# MIC3.net
KiCad netlist of a schematic drawn in Altium Designer
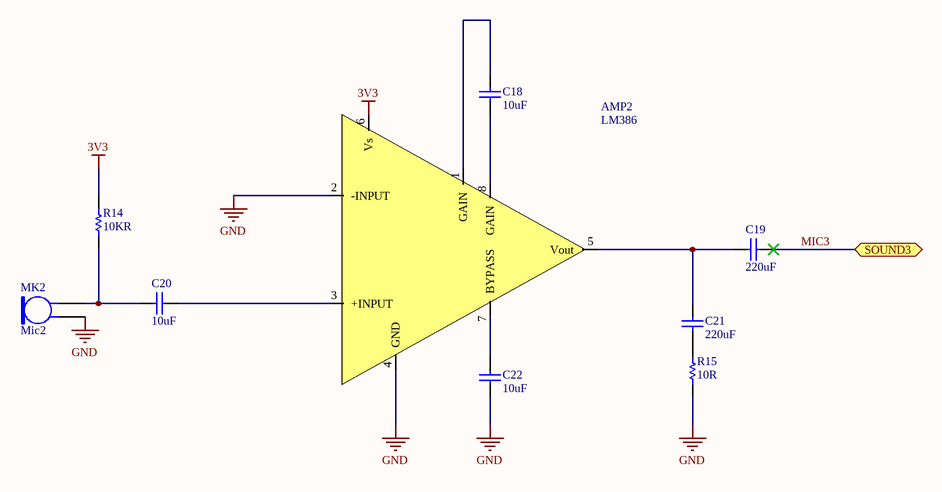
[diagram p0: MIC3.SchDoc]

(export (version "E")
  (design (tool "Eeschema 10.0.6"))
  (components
    (comp (ref "AMP2") (value "LM386") (footprint "Ampli") (libsource (lib "SCHLIB_Autobot") (part "LM386")))
    (comp (ref "C18")
      (value "10uF")
      (footprint "CAPC1608N")
      (description "Capacitor")
      (fields (field (name "PUBLISHER") "Altium Limited"))
      (libsource (lib "Miscellaneous Devices") (part "Cap"))
    )
    (comp (ref "C19")
      (value "220uF")
      (footprint "CAPC1608N")
      (description "Capacitor")
      (fields (field (name "PUBLISHER") "Altium Limited"))
      (libsource (lib "Miscellaneous Devices") (part "Cap"))
    )
    (comp (ref "C20")
      (value "10uF")
      (footprint "CAPC1608N")
      (description "Capacitor")
      (fields (field (name "PUBLISHER") "Altium Limited"))
      (libsource (lib "Miscellaneous Devices") (part "Cap"))
    )
    (comp (ref "C21")
      (value "220uF")
      (footprint "CAPC1608N")
      (description "Capacitor")
      (fields (field (name "PUBLISHER") "Altium Limited"))
      (libsource (lib "Miscellaneous Devices") (part "Cap"))
    )
    (comp (ref "C22")
      (value "10uF")
      (footprint "CAPC1608N")
      (description "Capacitor")
      (fields (field (name "PUBLISHER") "Altium Limited"))
      (libsource (lib "Miscellaneous Devices") (part "Cap"))
    )
    (comp (ref "MK2")
      (value "Mic2")
      (footprint "PIN2")
      (description "Microphone")
      (fields (field (name "PUBLISHER") "Altium Limited"))
      (libsource (lib "Miscellaneous Devices") (part "Mic2"))
    )
    (comp (ref "R14")
      (value "10KR")
      (footprint "RESC1608N")
      (description "Resistor")
      (fields (field (name "PUBLISHER") "Altium Limited"))
      (libsource (lib "Miscellaneous Devices") (part "Res1"))
    )
    (comp (ref "R15")
      (value "10R")
      (footprint "RESC1608N")
      (description "Resistor")
      (fields (field (name "PUBLISHER") "Altium Limited"))
      (libsource (lib "Miscellaneous Devices") (part "Res1"))
    )
  )
  (nets
    (net (code "1") (name "/MIC3") (class "Default")
      (node (ref "C19") (pin "1") (pinfunction "1_1") (pintype "passive+no_connect"))
    )
    (net (code "2") (name "3V3") (class "Default")
      (node (ref "AMP2") (pin "6") (pinfunction "Vs_6") (pintype "passive"))
      (node (ref "R14") (pin "1") (pinfunction "1_1") (pintype "passive"))
    )
    (net (code "3") (name "GND") (class "Default")
      (node (ref "AMP2") (pin "2") (pinfunction "-INPUT_2") (pintype "passive"))
      (node (ref "AMP2") (pin "4") (pinfunction "GND_4") (pintype "passive"))
      (node (ref "C22") (pin "2") (pinfunction "2_2") (pintype "passive"))
      (node (ref "MK2") (pin "1") (pinfunction "1_1") (pintype "passive"))
      (node (ref "R15") (pin "2") (pinfunction "2_2") (pintype "passive"))
    )
    (net (code "4") (name "Net-(AMP2-+INPUT)") (class "Default")
      (node (ref "AMP2") (pin "3") (pinfunction "+INPUT_3") (pintype "passive"))
      (node (ref "C20") (pin "1") (pinfunction "1_1") (pintype "passive"))
    )
    (net (code "5") (name "Net-(AMP2-BYPASS)") (class "Default")
      (node (ref "AMP2") (pin "7") (pinfunction "BYPASS_7") (pintype "passive"))
      (node (ref "C22") (pin "1") (pinfunction "1_1") (pintype "passive"))
    )
    (net (code "6") (name "Net-(AMP2-GAIN-Pad1)") (class "Default")
      (node (ref "AMP2") (pin "1") (pinfunction "GAIN_1") (pintype "passive"))
      (node (ref "C18") (pin "1") (pinfunction "1_1") (pintype "passive"))
    )
    (net (code "7") (name "Net-(AMP2-GAIN-Pad8)") (class "Default")
      (node (ref "AMP2") (pin "8") (pinfunction "GAIN_8") (pintype "passive"))
      (node (ref "C18") (pin "2") (pinfunction "2_2") (pintype "passive"))
    )
    (net (code "8") (name "Net-(AMP2-Vout)") (class "Default")
      (node (ref "AMP2") (pin "5") (pinfunction "Vout_5") (pintype "passive"))
      (node (ref "C19") (pin "2") (pinfunction "2_2") (pintype "passive"))
      (node (ref "C21") (pin "1") (pinfunction "1_1") (pintype "passive"))
    )
    (net (code "9") (name "Net-(C20-Pad2)") (class "Default")
      (node (ref "C20") (pin "2") (pinfunction "2_2") (pintype "passive"))
      (node (ref "MK2") (pin "2") (pinfunction "2_2") (pintype "passive"))
      (node (ref "R14") (pin "2") (pinfunction "2_2") (pintype "passive"))
    )
    (net (code "10") (name "Net-(C21-Pad2)") (class "Default")
      (node (ref "C21") (pin "2") (pinfunction "2_2") (pintype "passive"))
      (node (ref "R15") (pin "1") (pinfunction "1_1") (pintype "passive"))
    )
  )
)
